# Heating_Datalogger.net
KiCad netlist of a schematic drawn in EAGLE
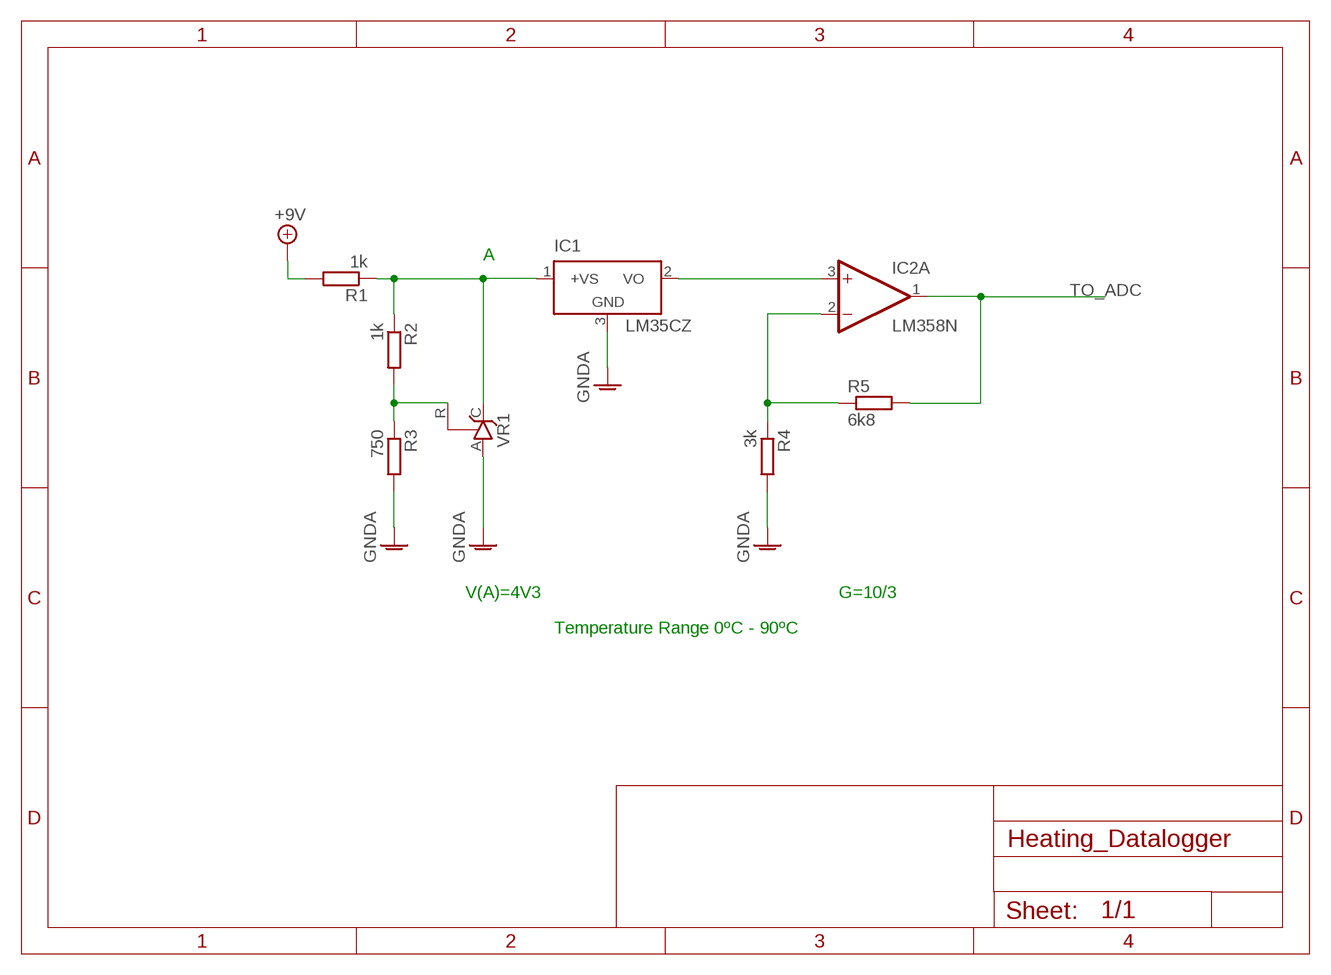
[diagram p0: schematic, sheet 1]

(export (version "E")
  (design (tool "Eeschema 10.0.6"))
  (components
    (comp (ref "IC1")
      (value "LM35CZ")
      (footprint "eagle-import:TO92")
      (libsource (lib "eagle-import") (part "LM35CZ"))
    )
    (comp (ref "IC2")
      (value "LM358N")
      (footprint "eagle-import:DIL08")
      (libsource (lib "eagle-import") (part "LM358N"))
    )
    (comp (ref "R1")
      (value "1k")
      (footprint "eagle-import:0204_5")
      (libsource (lib "eagle-import") (part "R-EU_0204/5"))
    )
    (comp (ref "R2")
      (value "1k")
      (footprint "eagle-import:0204_5")
      (libsource (lib "eagle-import") (part "R-EU_0204/5"))
    )
    (comp (ref "R3")
      (value "750")
      (footprint "eagle-import:0204_5")
      (libsource (lib "eagle-import") (part "R-EU_0204/5"))
    )
    (comp (ref "R4")
      (value "3k")
      (footprint "eagle-import:0204_5")
      (libsource (lib "eagle-import") (part "R-EU_0204/5"))
    )
    (comp (ref "R5")
      (value "6k8")
      (footprint "eagle-import:0204_5")
      (libsource (lib "eagle-import") (part "R-EU_0204/5"))
    )
    (comp (ref "VR1")
      (value "TL431CLP")
      (footprint "eagle-import:TO92-CLP")
      (libsource (lib "eagle-import") (part "TL431CLP"))
    )
  )
  (nets
    (net (code "1") (name "+9V") (class "Default")
      (node (ref "R1") (pin "2") (pinfunction "2_2") (pintype "passive"))
    )
    (net (code "2") (name "/TO_ADC") (class "Default")
      (node (ref "IC2") (pin "1") (pinfunction "OUT_1") (pintype "output"))
      (node (ref "R5") (pin "2") (pinfunction "2_2") (pintype "passive"))
    )
    (net (code "3") (name "GNDA") (class "Default")
      (node (ref "IC1") (pin "3") (pinfunction "GND_3") (pintype "power_in"))
      (node (ref "R3") (pin "2") (pinfunction "2_2") (pintype "passive"))
      (node (ref "R4") (pin "2") (pinfunction "2_2") (pintype "passive"))
      (node (ref "VR1") (pin "A") (pinfunction "A_A") (pintype "passive"))
    )
    (net (code "4") (name "Net-(IC1-+VS)") (class "Default")
      (node (ref "IC1") (pin "1") (pinfunction "+VS_1") (pintype "input"))
      (node (ref "R1") (pin "1") (pinfunction "1_1") (pintype "passive"))
      (node (ref "R2") (pin "1") (pinfunction "1_1") (pintype "passive"))
      (node (ref "VR1") (pin "C") (pinfunction "C_C") (pintype "passive"))
    )
    (net (code "5") (name "Net-(IC1-VO)") (class "Default")
      (node (ref "IC1") (pin "2") (pinfunction "VO_2") (pintype "input"))
      (node (ref "IC2") (pin "3") (pinfunction "+IN_3") (pintype "input"))
    )
    (net (code "6") (name "Net-(IC2A--IN)") (class "Default")
      (node (ref "IC2") (pin "2") (pinfunction "-IN_2") (pintype "input"))
      (node (ref "R4") (pin "1") (pinfunction "1_1") (pintype "passive"))
      (node (ref "R5") (pin "1") (pinfunction "1_1") (pintype "passive"))
    )
    (net (code "7") (name "Net-(R2-Pad2)") (class "Default")
      (node (ref "R2") (pin "2") (pinfunction "2_2") (pintype "passive"))
      (node (ref "R3") (pin "1") (pinfunction "1_1") (pintype "passive"))
      (node (ref "VR1") (pin "R") (pinfunction "R_R") (pintype "passive"))
    )
  )
)
